# GSM.net
KiCad netlist of a schematic drawn in Altium Designer
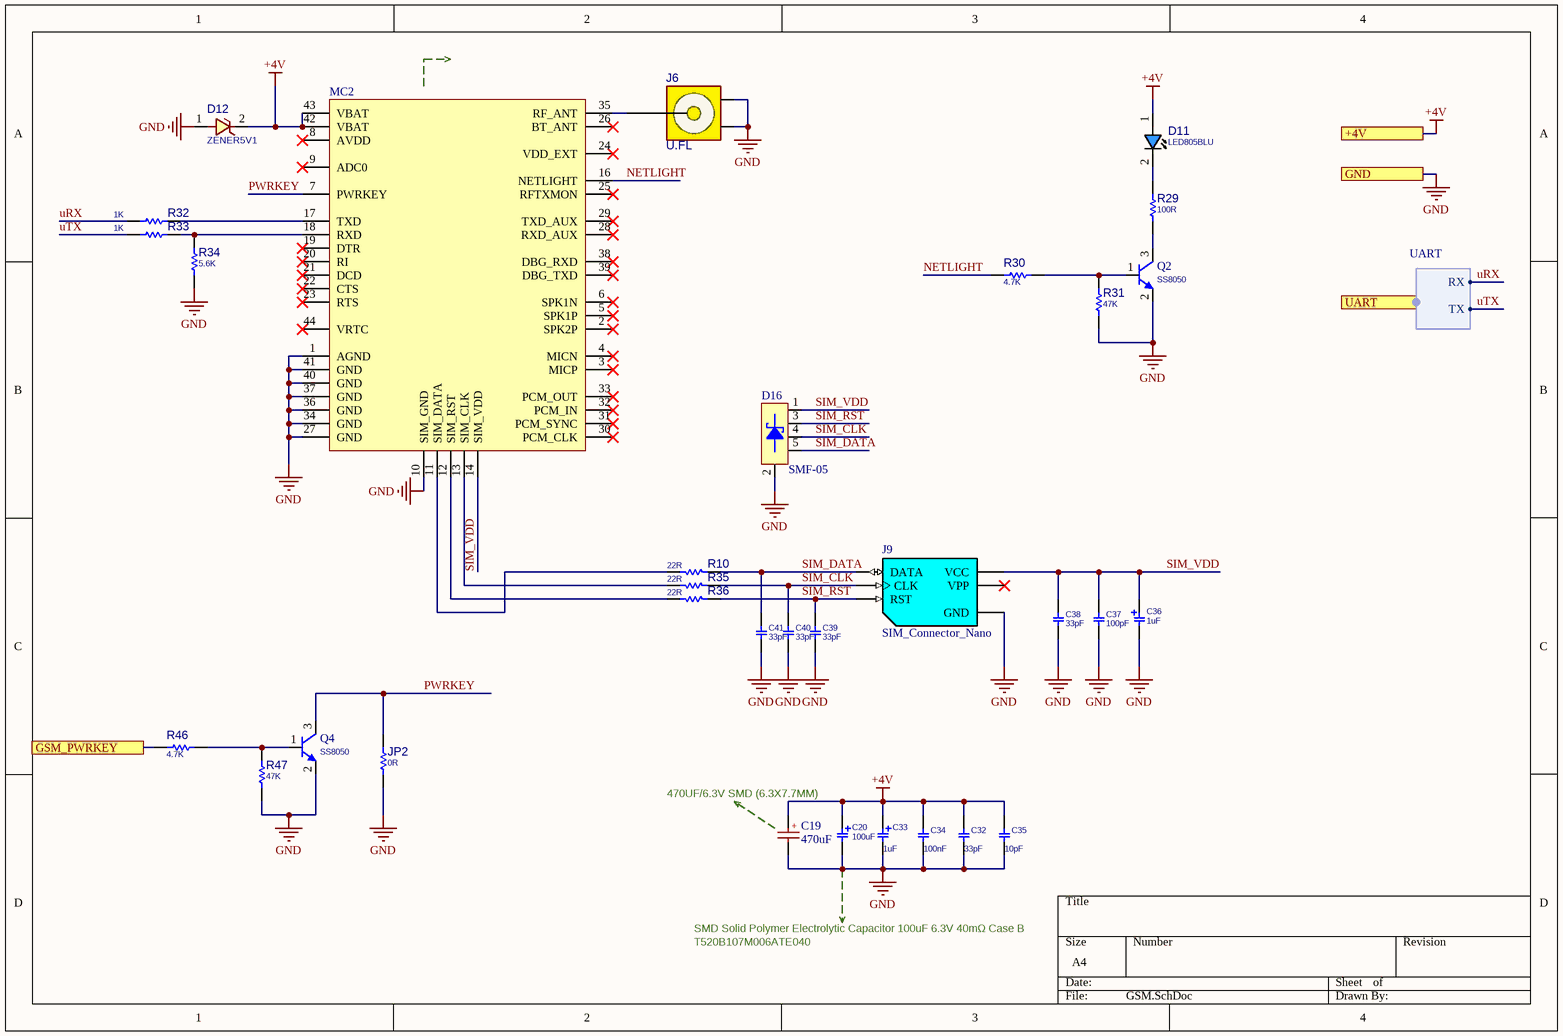
[diagram p0: GSM.SchDoc]

(export (version "E")
  (design (tool "Eeschema 10.0.6"))
  (components
    (comp (ref "C19")
      (value "470uF")
      (footprint "Cap SMD 6.3x7.7mm")
      (description "SMD Aluminum Electrolytic Capacitor")
      (fields
        (field (name "VOLTAGE") "12v")
        (field (name "TOLERANCE") "5%")
        (field (name "PUBLISHER") "Majid Derhambakhsh")
      )
      (libsource (lib "mBedLab Altium Library (2024-04-20)") (part "CAP Electrolytic SMD"))
    )
    (comp (ref "C20")
      (value "100uF")
      (footprint "C_TN_3528_BLK")
      (description "CAP, SMD, TAN")
      (fields (field (name "MANF") "VISHAY") (field (name "MANF_P#") "T55A106M6R3C0300"))
      (libsource (lib "AVR_RCS") (part "CAP_SMD_TAN_4"))
    )
    (comp (ref "C32")
      (value "33pF")
      (footprint "C0603")
      (description "CAP, MLCC, -F, -V, MATERIAL, -%, 0201")
      (fields (field (name "MANF_P#") "MANF_PART#"))
      (libsource (lib "passive_smd") (part "CAP_SMD_MLCC_0603"))
    )
    (comp (ref "C33")
      (value "1uF")
      (footprint "C_TN_3216")
      (description "CAP, SMD, TAN,")
      (libsource (lib "passive_smd") (part "CAP_SMD_TAN"))
    )
    (comp (ref "C34")
      (value "100nF")
      (footprint "C0805")
      (description "CAP, MLCC, -F, -V, MATERIAL, -%, 0201")
      (fields (field (name "MANF_P#") "MANF_PART#"))
      (libsource (lib "passive_smd") (part "CAP_SMD_MLCC_0805"))
    )
    (comp (ref "C35")
      (value "10pF")
      (footprint "C0603")
      (description "CAP, MLCC, -F, -V, MATERIAL, -%, 0201")
      (fields (field (name "MANF_P#") "MANF_PART#"))
      (libsource (lib "passive_smd") (part "CAP_SMD_MLCC_0603"))
    )
    (comp (ref "C36")
      (value "1uF")
      (footprint "C_TN_3216")
      (description "CAP, SMD, TAN,")
      (libsource (lib "passive_smd") (part "CAP_SMD_TAN"))
    )
    (comp (ref "C37")
      (value "100pF")
      (footprint "C0805")
      (description "CAP, MLCC, -F, -V, MATERIAL, -%, 0201")
      (fields (field (name "MANF_P#") "MANF_PART#"))
      (libsource (lib "passive_smd") (part "CAP_SMD_MLCC_0805"))
    )
    (comp (ref "C38")
      (value "33pF")
      (footprint "C0805")
      (description "CAP, MLCC, -F, -V, MATERIAL, -%, 0201")
      (fields (field (name "MANF_P#") "MANF_PART#"))
      (libsource (lib "passive_smd") (part "CAP_SMD_MLCC_0805"))
    )
    (comp (ref "C39")
      (value "33pF")
      (footprint "C0805")
      (description "CAP, MLCC, -F, -V, MATERIAL, -%, 0201")
      (fields (field (name "MANF_P#") "MANF_PART#"))
      (libsource (lib "passive_smd") (part "CAP_SMD_MLCC_0805"))
    )
    (comp (ref "C40")
      (value "33pF")
      (footprint "C0805")
      (description "CAP, MLCC, -F, -V, MATERIAL, -%, 0201")
      (fields (field (name "MANF_P#") "MANF_PART#"))
      (libsource (lib "passive_smd") (part "CAP_SMD_MLCC_0805"))
    )
    (comp (ref "C41")
      (value "33pF")
      (footprint "C0805")
      (description "CAP, MLCC, -F, -V, MATERIAL, -%, 0201")
      (fields (field (name "MANF_P#") "MANF_PART#"))
      (libsource (lib "passive_smd") (part "CAP_SMD_MLCC_0805"))
    )
    (comp (ref "D11")
      (value "LED805BLU")
      (footprint "LED0805BLU")
      (description "LED, SMD, 0805, BLUE")
      (fields (field (name "MANF") "MANF") (field (name "MANF_P#") "MANF_PART#"))
      (libsource (lib "led(diode)") (part "LED_SMD_0805_BLU"))
    )
    (comp (ref "D12")
      (value "ZENER5V1")
      (footprint "D_SOD123W")
      (description "DIODE, ZENER, 1W, 5.1V")
      (fields (field (name "MANF") "Diodes") (field (name "MANF_P#") "BZT52HC5V1WF-7"))
      (libsource (lib "AVR_RCS") (part "DIODE_SMD_ZENER_BZT52HC5V1"))
    )
    (comp (ref "D16")
      (value "SMF-05")
      (footprint "SC70-5_N")
      (description "TVS Diode Array")
      (fields (field (name "VALIDATION") "Valid"))
      (libsource (lib "AVR_RCS") (part "Semi_Diod_TVS_SMF05"))
    )
    (comp (ref "J6")
      (value "U.FL")
      (footprint "UFL")
      (description "CONN, RF, U.FL, STRAIGHT, Ultra Miniature Coaxial")
      (fields
        (field (name "MANF_P#") "CONUFL001-SMD, U.FL-R-SMT-1(10), 128-0711-201")
        (field (name "MANF") "Linx, Hirose, Cinch")
      )
      (libsource (lib "conn_rf") (part "CONN_RF_UFL"))
    )
    (comp (ref "J9")
      (value "SIM_Connector_Nano")
      (footprint "SIM_Connector_Nano")
      (description "Nano SimCard Holder 6P")
      (libsource (lib "Mehrdad") (part "SIM_Connector_Nano"))
    )
    (comp (ref "JP2")
      (value "0R")
      (footprint "R0805")
      (description "RESISTOR, SMD")
      (libsource (lib "passive_smd") (part "RES_SMD_0805"))
    )
    (comp (ref "MC2")
      (value "M66")
      (footprint "m66")
      (description "Quectel GSM/GPRS Module")
      (fields (field (name "VALIDATION") "Valid"))
      (libsource (lib "AVR_RCS") (part "ModSen_Com_M66"))
    )
    (comp (ref "Q2")
      (value "SS8050")
      (footprint "SOT23_3")
      (description "BJT, NPN, 25v, 1.5A, SMD, SOT23")
      (fields (field (name "MANF") "GALAXY"))
      (libsource (lib "transistor_bjt") (part "NPN_SS8050_SOT23"))
    )
    (comp (ref "Q4")
      (value "SS8050")
      (footprint "SOT23_3")
      (description "BJT, NPN, 25v, 1.5A, SMD, SOT23")
      (fields (field (name "MANF") "GALAXY"))
      (libsource (lib "transistor_bjt") (part "NPN_SS8050_SOT23"))
    )
    (comp (ref "R10")
      (value "22R")
      (footprint "R0805")
      (description "RESISTOR, SMD")
      (libsource (lib "passive_smd") (part "RES_SMD_0805"))
    )
    (comp (ref "R29")
      (value "100R")
      (footprint "R0805")
      (description "RESISTOR, SMD")
      (libsource (lib "passive_smd") (part "RES_SMD_0805"))
    )
    (comp (ref "R30")
      (value "4.7K")
      (footprint "R0805")
      (description "RESISTOR, SMD")
      (libsource (lib "passive_smd") (part "RES_SMD_0805"))
    )
    (comp (ref "R31")
      (value "47K")
      (footprint "R0805")
      (description "RESISTOR, SMD")
      (libsource (lib "passive_smd") (part "RES_SMD_0805"))
    )
    (comp (ref "R32")
      (value "1K")
      (footprint "R0805")
      (description "RESISTOR, SMD")
      (libsource (lib "passive_smd") (part "RES_SMD_0805"))
    )
    (comp (ref "R33")
      (value "1K")
      (footprint "R0805")
      (description "RESISTOR, SMD")
      (libsource (lib "passive_smd") (part "RES_SMD_0805"))
    )
    (comp (ref "R34")
      (value "5.6K")
      (footprint "R0805")
      (description "RESISTOR, SMD")
      (libsource (lib "passive_smd") (part "RES_SMD_0805"))
    )
    (comp (ref "R35")
      (value "22R")
      (footprint "R0805")
      (description "RESISTOR, SMD")
      (libsource (lib "passive_smd") (part "RES_SMD_0805"))
    )
    (comp (ref "R36")
      (value "22R")
      (footprint "R0805")
      (description "RESISTOR, SMD")
      (libsource (lib "passive_smd") (part "RES_SMD_0805"))
    )
    (comp (ref "R46")
      (value "4.7K")
      (footprint "R0805")
      (description "RESISTOR, SMD")
      (libsource (lib "passive_smd") (part "RES_SMD_0805"))
    )
    (comp (ref "R47")
      (value "47K")
      (footprint "R0805")
      (description "RESISTOR, SMD")
      (libsource (lib "passive_smd") (part "RES_SMD_0805"))
    )
  )
  (nets
    (net (code "2") (name "+4V") (class "Default")
      (node (ref "C19") (pin "1") (pinfunction "+_1") (pintype "passive"))
      (node (ref "C20") (pin "1") (pinfunction "1_1") (pintype "passive"))
      (node (ref "C32") (pin "1") (pinfunction "1_1") (pintype "passive"))
      (node (ref "C33") (pin "1") (pinfunction "1_1") (pintype "passive"))
      (node (ref "C34") (pin "2") (pinfunction "2_2") (pintype "passive"))
      (node (ref "C35") (pin "1") (pinfunction "1_1") (pintype "passive"))
      (node (ref "D11") (pin "1") (pinfunction "ANODE_1") (pintype "passive"))
      (node (ref "D12") (pin "2") (pinfunction "2_2") (pintype "passive"))
      (node (ref "MC2") (pin "42") (pinfunction "VBAT_42") (pintype "passive"))
      (node (ref "MC2") (pin "43") (pinfunction "VBAT_43") (pintype "passive"))
    )
    (net (code "3") (name "/GSM_PWRKEY") (class "Default")
      (node (ref "R46") (pin "1") (pinfunction "1_1") (pintype "passive"))
    )
    (net (code "4") (name "/NETLIGHT") (class "Default")
      (node (ref "MC2") (pin "16") (pinfunction "NETLIGHT_16") (pintype "passive"))
      (node (ref "R30") (pin "1") (pinfunction "1_1") (pintype "passive"))
    )
    (net (code "5") (name "/PWRKEY") (class "Default")
      (node (ref "JP2") (pin "2") (pinfunction "2_2") (pintype "passive"))
      (node (ref "MC2") (pin "7") (pinfunction "PWRKEY_7") (pintype "passive"))
      (node (ref "Q4") (pin "3") (pinfunction "C_3") (pintype "passive"))
    )
    (net (code "6") (name "/SIM_CLK") (class "Default")
      (node (ref "C40") (pin "2") (pinfunction "2_2") (pintype "passive"))
      (node (ref "D16") (pin "4") (pinfunction "K_4") (pintype "passive"))
      (node (ref "J9") (pin "C3") (pinfunction "CLK_C3") (pintype "input"))
      (node (ref "R35") (pin "1") (pinfunction "1_1") (pintype "passive"))
    )
    (net (code "7") (name "/SIM_DATA") (class "Default")
      (node (ref "C41") (pin "2") (pinfunction "2_2") (pintype "passive"))
      (node (ref "D16") (pin "5") (pinfunction "K_5") (pintype "passive"))
      (node (ref "J9") (pin "C7") (pinfunction "DATA_C7") (pintype "bidirectional"))
      (node (ref "R10") (pin "1") (pinfunction "1_1") (pintype "passive"))
    )
    (net (code "8") (name "/SIM_RST") (class "Default")
      (node (ref "C39") (pin "2") (pinfunction "2_2") (pintype "passive"))
      (node (ref "D16") (pin "3") (pinfunction "K_3") (pintype "passive"))
      (node (ref "J9") (pin "C2") (pinfunction "RST_C2") (pintype "input"))
      (node (ref "R36") (pin "1") (pinfunction "1_1") (pintype "passive"))
    )
    (net (code "9") (name "/SIM_VDD") (class "Default")
      (node (ref "C36") (pin "1") (pinfunction "1_1") (pintype "passive"))
      (node (ref "C37") (pin "2") (pinfunction "2_2") (pintype "passive"))
      (node (ref "C38") (pin "2") (pinfunction "2_2") (pintype "passive"))
      (node (ref "D16") (pin "1") (pinfunction "K_1") (pintype "passive"))
      (node (ref "J9") (pin "C1") (pinfunction "VCC_C1") (pintype "power_in"))
      (node (ref "MC2") (pin "14") (pinfunction "SIM_VDD_14") (pintype "passive"))
    )
    (net (code "10") (name "/uRX") (class "Default")
      (node (ref "R32") (pin "1") (pinfunction "1_1") (pintype "passive"))
    )
    (net (code "11") (name "/uTX") (class "Default")
      (node (ref "R33") (pin "1") (pinfunction "1_1") (pintype "passive"))
    )
    (net (code "13") (name "GND") (class "Default")
      (node (ref "C19") (pin "2") (pinfunction "-_2") (pintype "passive"))
      (node (ref "C20") (pin "2") (pinfunction "2_2") (pintype "passive"))
      (node (ref "C32") (pin "2") (pinfunction "2_2") (pintype "passive"))
      (node (ref "C33") (pin "2") (pinfunction "2_2") (pintype "passive"))
      (node (ref "C34") (pin "1") (pinfunction "1_1") (pintype "passive"))
      (node (ref "C35") (pin "2") (pinfunction "2_2") (pintype "passive"))
      (node (ref "C36") (pin "2") (pinfunction "2_2") (pintype "passive"))
      (node (ref "C37") (pin "1") (pinfunction "1_1") (pintype "passive"))
      (node (ref "C38") (pin "1") (pinfunction "1_1") (pintype "passive"))
      (node (ref "C39") (pin "1") (pinfunction "1_1") (pintype "passive"))
      (node (ref "C40") (pin "1") (pinfunction "1_1") (pintype "passive"))
      (node (ref "C41") (pin "1") (pinfunction "1_1") (pintype "passive"))
      (node (ref "D12") (pin "1") (pinfunction "1_1") (pintype "passive"))
      (node (ref "D16") (pin "2") (pinfunction "K_2") (pintype "passive"))
      (node (ref "J6") (pin "2") (pinfunction "G1_2") (pintype "passive"))
      (node (ref "J6") (pin "3") (pinfunction "G2_3") (pintype "passive"))
      (node (ref "J9") (pin "C5") (pinfunction "GND_C5") (pintype "power_in"))
      (node (ref "JP2") (pin "1") (pinfunction "1_1") (pintype "passive"))
      (node (ref "MC2") (pin "1") (pinfunction "AGND_1") (pintype "passive"))
      (node (ref "MC2") (pin "10") (pinfunction "SIM_GND_10") (pintype "passive"))
      (node (ref "MC2") (pin "27") (pinfunction "GND_27") (pintype "passive"))
      (node (ref "MC2") (pin "34") (pinfunction "GND_34") (pintype "passive"))
      (node (ref "MC2") (pin "36") (pinfunction "GND_36") (pintype "passive"))
      (node (ref "MC2") (pin "37") (pinfunction "GND_37") (pintype "passive"))
      (node (ref "MC2") (pin "40") (pinfunction "GND_40") (pintype "passive"))
      (node (ref "MC2") (pin "41") (pinfunction "GND_41") (pintype "passive"))
      (node (ref "Q2") (pin "2") (pinfunction "E_2") (pintype "passive"))
      (node (ref "Q4") (pin "2") (pinfunction "E_2") (pintype "passive"))
      (node (ref "R31") (pin "1") (pinfunction "1_1") (pintype "passive"))
      (node (ref "R34") (pin "1") (pinfunction "1_1") (pintype "passive"))
      (node (ref "R47") (pin "1") (pinfunction "1_1") (pintype "passive"))
    )
    (net (code "14") (name "Net-(D11-CATHODE)") (class "Default")
      (node (ref "D11") (pin "2") (pinfunction "CATHODE_2") (pintype "passive"))
      (node (ref "R29") (pin "2") (pinfunction "2_2") (pintype "passive"))
    )
    (net (code "15") (name "Net-(J6-SIG)") (class "Default")
      (node (ref "J6") (pin "1") (pinfunction "SIG_1") (pintype "passive"))
      (node (ref "MC2") (pin "35") (pinfunction "RF_ANT_35") (pintype "passive"))
    )
    (net (code "16") (name "Net-(MC2-RXD)") (class "Default")
      (node (ref "MC2") (pin "18") (pinfunction "RXD_18") (pintype "passive"))
      (node (ref "R33") (pin "2") (pinfunction "2_2") (pintype "passive"))
      (node (ref "R34") (pin "2") (pinfunction "2_2") (pintype "passive"))
    )
    (net (code "17") (name "Net-(MC2-SIM_CLK)") (class "Default")
      (node (ref "MC2") (pin "13") (pinfunction "SIM_CLK_13") (pintype "passive"))
      (node (ref "R35") (pin "2") (pinfunction "2_2") (pintype "passive"))
    )
    (net (code "18") (name "Net-(MC2-SIM_DATA)") (class "Default")
      (node (ref "MC2") (pin "11") (pinfunction "SIM_DATA_11") (pintype "passive"))
      (node (ref "R10") (pin "2") (pinfunction "2_2") (pintype "passive"))
    )
    (net (code "19") (name "Net-(MC2-SIM_RST)") (class "Default")
      (node (ref "MC2") (pin "12") (pinfunction "SIM_RST_12") (pintype "passive"))
      (node (ref "R36") (pin "2") (pinfunction "2_2") (pintype "passive"))
    )
    (net (code "20") (name "Net-(MC2-TXD)") (class "Default")
      (node (ref "MC2") (pin "17") (pinfunction "TXD_17") (pintype "passive"))
      (node (ref "R32") (pin "2") (pinfunction "2_2") (pintype "passive"))
    )
    (net (code "21") (name "Net-(Q2-B)") (class "Default")
      (node (ref "Q2") (pin "1") (pinfunction "B_1") (pintype "passive"))
      (node (ref "R30") (pin "2") (pinfunction "2_2") (pintype "passive"))
      (node (ref "R31") (pin "2") (pinfunction "2_2") (pintype "passive"))
    )
    (net (code "22") (name "Net-(Q2-C)") (class "Default")
      (node (ref "Q2") (pin "3") (pinfunction "C_3") (pintype "passive"))
      (node (ref "R29") (pin "1") (pinfunction "1_1") (pintype "passive"))
    )
    (net (code "23") (name "Net-(Q4-B)") (class "Default")
      (node (ref "Q4") (pin "1") (pinfunction "B_1") (pintype "passive"))
      (node (ref "R46") (pin "2") (pinfunction "2_2") (pintype "passive"))
      (node (ref "R47") (pin "2") (pinfunction "2_2") (pintype "passive"))
    )
    (net (code "24") (name "unconnected-(J9-VPP-PadC6)") (class "Default")
      (node (ref "J9") (pin "C6") (pinfunction "VPP_C6") (pintype "power_in+no_connect"))
    )
    (net (code "25") (name "unconnected-(MC2-ADC0-Pad9)") (class "Default")
      (node (ref "MC2") (pin "9") (pinfunction "ADC0_9") (pintype "passive+no_connect"))
    )
    (net (code "26") (name "unconnected-(MC2-AVDD-Pad8)") (class "Default")
      (node (ref "MC2") (pin "8") (pinfunction "AVDD_8") (pintype "passive+no_connect"))
    )
    (net (code "27") (name "unconnected-(MC2-BT_ANT-Pad26)") (class "Default")
      (node (ref "MC2") (pin "26") (pinfunction "BT_ANT_26") (pintype "passive+no_connect"))
    )
    (net (code "28") (name "unconnected-(MC2-CTS-Pad22)") (class "Default")
      (node (ref "MC2") (pin "22") (pinfunction "CTS_22") (pintype "passive+no_connect"))
    )
    (net (code "29") (name "unconnected-(MC2-DBG_RXD-Pad38)") (class "Default")
      (node (ref "MC2") (pin "38") (pinfunction "DBG_RXD_38") (pintype "passive+no_connect"))
    )
    (net (code "30") (name "unconnected-(MC2-DBG_TXD-Pad39)") (class "Default")
      (node (ref "MC2") (pin "39") (pinfunction "DBG_TXD_39") (pintype "passive+no_connect"))
    )
    (net (code "31") (name "unconnected-(MC2-DCD-Pad21)") (class "Default")
      (node (ref "MC2") (pin "21") (pinfunction "DCD_21") (pintype "passive+no_connect"))
    )
    (net (code "32") (name "unconnected-(MC2-DTR-Pad19)") (class "Default")
      (node (ref "MC2") (pin "19") (pinfunction "DTR_19") (pintype "passive+no_connect"))
    )
    (net (code "33") (name "unconnected-(MC2-MICN-Pad4)") (class "Default")
      (node (ref "MC2") (pin "4") (pinfunction "MICN_4") (pintype "passive+no_connect"))
    )
    (net (code "34") (name "unconnected-(MC2-MICP-Pad3)") (class "Default")
      (node (ref "MC2") (pin "3") (pinfunction "MICP_3") (pintype "passive+no_connect"))
    )
    (net (code "35") (name "unconnected-(MC2-PCM_CLK-Pad30)") (class "Default")
      (node (ref "MC2") (pin "30") (pinfunction "PCM_CLK_30") (pintype "passive+no_connect"))
    )
    (net (code "36") (name "unconnected-(MC2-PCM_IN-Pad32)") (class "Default")
      (node (ref "MC2") (pin "32") (pinfunction "PCM_IN_32") (pintype "passive+no_connect"))
    )
    (net (code "37") (name "unconnected-(MC2-PCM_OUT-Pad33)") (class "Default")
      (node (ref "MC2") (pin "33") (pinfunction "PCM_OUT_33") (pintype "passive+no_connect"))
    )
    (net (code "38") (name "unconnected-(MC2-PCM_SYNC-Pad31)") (class "Default")
      (node (ref "MC2") (pin "31") (pinfunction "PCM_SYNC_31") (pintype "passive+no_connect"))
    )
    (net (code "39") (name "unconnected-(MC2-RFTXMON-Pad25)") (class "Default")
      (node (ref "MC2") (pin "25") (pinfunction "RFTXMON_25") (pintype "passive+no_connect"))
    )
    (net (code "40") (name "unconnected-(MC2-RI-Pad20)") (class "Default")
      (node (ref "MC2") (pin "20") (pinfunction "RI_20") (pintype "passive+no_connect"))
    )
    (net (code "41") (name "unconnected-(MC2-RTS-Pad23)") (class "Default")
      (node (ref "MC2") (pin "23") (pinfunction "RTS_23") (pintype "passive+no_connect"))
    )
    (net (code "42") (name "unconnected-(MC2-RXD_AUX-Pad28)") (class "Default")
      (node (ref "MC2") (pin "28") (pinfunction "RXD_AUX_28") (pintype "passive+no_connect"))
    )
    (net (code "43") (name "unconnected-(MC2-SPK1N-Pad6)") (class "Default")
      (node (ref "MC2") (pin "6") (pinfunction "SPK1N_6") (pintype "passive+no_connect"))
    )
    (net (code "44") (name "unconnected-(MC2-SPK1P-Pad5)") (class "Default")
      (node (ref "MC2") (pin "5") (pinfunction "SPK1P_5") (pintype "passive+no_connect"))
    )
    (net (code "45") (name "unconnected-(MC2-SPK2P-Pad2)") (class "Default")
      (node (ref "MC2") (pin "2") (pinfunction "SPK2P_2") (pintype "passive+no_connect"))
    )
    (net (code "46") (name "unconnected-(MC2-TXD_AUX-Pad29)") (class "Default")
      (node (ref "MC2") (pin "29") (pinfunction "TXD_AUX_29") (pintype "passive+no_connect"))
    )
    (net (code "47") (name "unconnected-(MC2-VDD_EXT-Pad24)") (class "Default")
      (node (ref "MC2") (pin "24") (pinfunction "VDD_EXT_24") (pintype "passive+no_connect"))
    )
    (net (code "48") (name "unconnected-(MC2-VRTC-Pad44)") (class "Default")
      (node (ref "MC2") (pin "44") (pinfunction "VRTC_44") (pintype "passive+no_connect"))
    )
  )
)
